# Sheet3.net
KiCad netlist of a schematic drawn in Altium Designer
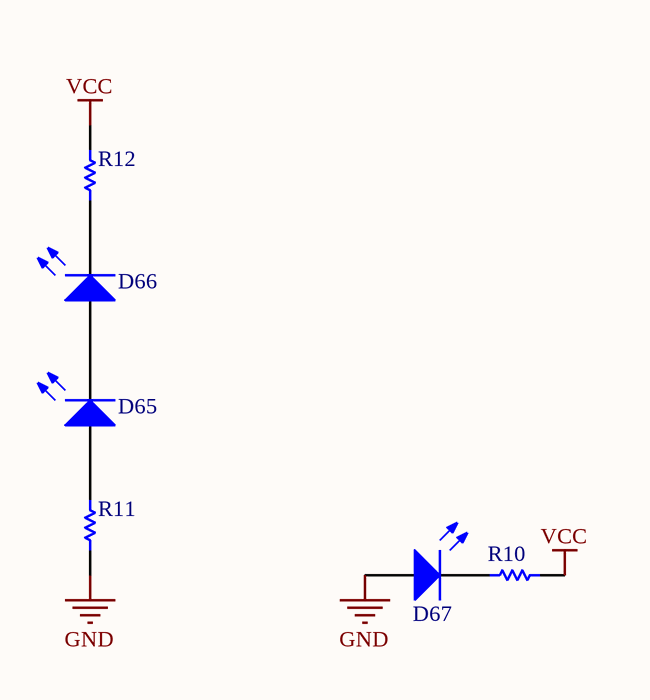
[diagram p0: Sheet3.SchDoc]

(export (version "E")
  (design (tool "Eeschema 10.0.6"))
  (components
    (comp (ref "D65")
      (value "LED 3mm")
      (footprint "LED-3mm")
      (description "Typical LED")
      (fields (field (name "DESIGNER") "Seyed Mohsen Ghasemian") (field (name "PUBLISHER") "www.picpars.com"))
      (libsource (lib "PicPars.com_usefully_Library (2)") (part "LED 3mm"))
    )
    (comp (ref "D66")
      (value "LED 3mm")
      (footprint "LED-3mm")
      (description "Typical LED")
      (fields (field (name "DESIGNER") "Seyed Mohsen Ghasemian") (field (name "PUBLISHER") "www.picpars.com"))
      (libsource (lib "PicPars.com_usefully_Library (2)") (part "LED 3mm"))
    )
    (comp (ref "D67")
      (value "LED 3mm")
      (footprint "LED-3mm")
      (description "Typical LED")
      (fields (field (name "DESIGNER") "Seyed Mohsen Ghasemian") (field (name "PUBLISHER") "www.picpars.com"))
      (libsource (lib "PicPars.com_usefully_Library (2)") (part "LED 3mm"))
    )
    (comp (ref "R10")
      (value "Resistor vertical")
      (footprint "Res50")
      (description "Resistor 0.5")
      (fields (field (name "PUBLISHER") "Seyed mohsen ghasemian"))
      (libsource (lib "PicPars.com_usefully_Library (2)") (part "Resistor vertical"))
    )
    (comp (ref "R11")
      (value "Resistor vertical")
      (footprint "Res50")
      (description "Resistor 0.5")
      (fields (field (name "PUBLISHER") "Seyed mohsen ghasemian"))
      (libsource (lib "PicPars.com_usefully_Library (2)") (part "Resistor vertical"))
    )
    (comp (ref "R12")
      (value "Resistor vertical")
      (footprint "Res50")
      (description "Resistor 0.5")
      (fields (field (name "PUBLISHER") "Seyed mohsen ghasemian"))
      (libsource (lib "PicPars.com_usefully_Library (2)") (part "Resistor vertical"))
    )
  )
  (nets
    (net (code "1") (name "GND") (class "Default")
      (node (ref "D67") (pin "1") (pinfunction "A_1") (pintype "passive"))
      (node (ref "R11") (pin "1") (pinfunction "1_1") (pintype "passive"))
    )
    (net (code "2") (name "Net-(D65-A)") (class "Default")
      (node (ref "D65") (pin "1") (pinfunction "A_1") (pintype "passive"))
      (node (ref "R11") (pin "2") (pinfunction "2_2") (pintype "passive"))
    )
    (net (code "3") (name "Net-(D65-K)") (class "Default")
      (node (ref "D65") (pin "2") (pinfunction "K_2") (pintype "passive"))
      (node (ref "D66") (pin "1") (pinfunction "A_1") (pintype "passive"))
    )
    (net (code "4") (name "Net-(D66-K)") (class "Default")
      (node (ref "D66") (pin "2") (pinfunction "K_2") (pintype "passive"))
      (node (ref "R12") (pin "1") (pinfunction "1_1") (pintype "passive"))
    )
    (net (code "5") (name "VCC") (class "Default")
      (node (ref "R10") (pin "2") (pinfunction "2_2") (pintype "passive"))
      (node (ref "R12") (pin "2") (pinfunction "2_2") (pintype "passive"))
    )
    (net (code "6") (name "unconnected-(D67-K-Pad2)") (class "Default")
      (node (ref "D67") (pin "2") (pinfunction "K_2") (pintype "passive"))
    )
    (net (code "7") (name "unconnected-(R10-Pad1)") (class "Default")
      (node (ref "R10") (pin "1") (pinfunction "1_1") (pintype "passive"))
    )
  )
)
